# Filtr3.net
KiCad netlist of a schematic drawn in Altium Designer
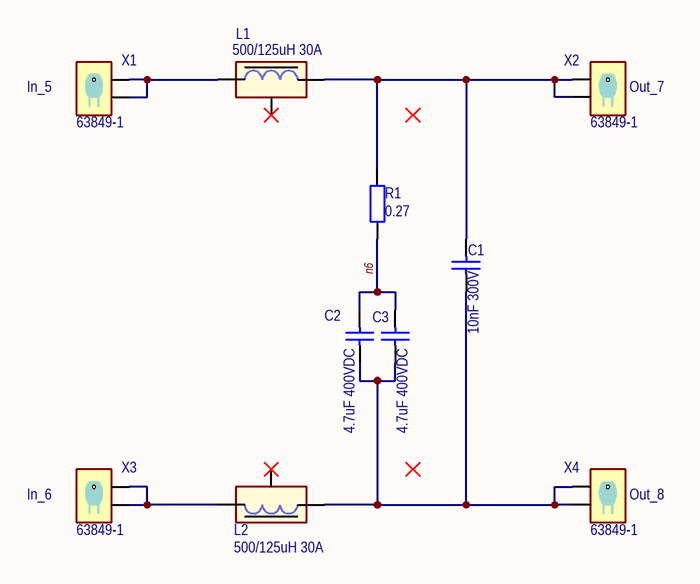
[diagram p0: Filtr3.SchDoc]

(export (version "E")
  (design (tool "Eeschema 10.0.6"))
  (components
    (comp (ref "C1")
      (value "10nF 300V")
      (footprint "mainLib:C Y2 D13 7.5b")
      (description "Ceramic D=14 LS=7.5 300VAC X1Y2")
      (fields (field (name "PARTNUMBER") "DE2F3KY103MA3") (field (name "MANUFACTURER") "Murata"))
      (libsource (lib "mainRCLib") (part "C X1Y2 10nF D13 LS7.5"))
    )
    (comp (ref "C2")
      (value "4.7uF 400VDC")
      (footprint "mainLib:MKP_W20_H39.5_L41.5_LS37.5")
      (description "Polypropelene W20 H39.5 L41.5 LS37.5 400VDC 10%")
      (fields (field (name "PARTNUMBER") "MKP1G044707G00K") (field (name "MANUFACTURER") "Wima"))
      (libsource (lib "mainRCLib") (part "MKP1 4.7uF 10% 400VDC"))
    )
    (comp (ref "C3")
      (value "4.7uF 400VDC")
      (footprint "mainLib:MKP_W20_H39.5_L41.5_LS37.5")
      (description "Polypropelene W20 H39.5 L41.5 LS37.5 400VDC 10%")
      (fields (field (name "PARTNUMBER") "MKP1G044707G00K") (field (name "MANUFACTURER") "Wima"))
      (libsource (lib "mainRCLib") (part "MKP1 4.7uF 10% 400VDC"))
    )
    (comp (ref "L1")
      (value "500/125uH 30A")
      (footprint "mainLib:Dross (500/125 uH 30 A)AMAK.671111.034")
      (description "500/125uH 30A  (Core T250-52 X1)")
      (fields (field (name "MANUFACTURER") "OLTEST") (field (name "PARTNUMBER") "АМАК.671111.034"))
      (libsource (lib "mainLib") (part "Dross 500/125uH 30A АМАК.671111.034"))
    )
    (comp (ref "L2")
      (value "500/125uH 30A")
      (footprint "mainLib:Dross (500/125 uH 30 A)AMAK.671111.034")
      (description "500/125uH 30A  (Core T250-52 X1)")
      (fields (field (name "MANUFACTURER") "OLTEST") (field (name "PARTNUMBER") "АМАК.671111.034"))
      (libsource (lib "") (part "Dross 500/125uH 30A АМАК.671111.034_1"))
    )
    (comp (ref "R1")
      (value "0.27")
      (footprint "mainLib:PRW 5W 1050")
      (description "Выводной PRW 5W 0R27 +-5%")
      (fields (field (name "PARTNUMBER") "PRW05WJW27K") (field (name "MANUFACTURER") "RoyalOhm"))
      (libsource (lib "mainRCLib") (part "PRW 0.27 5W +-5%"))
    )
    (comp (ref "X1")
      (value "63849-1")
      (footprint "63849-1+insulator(154719-1)")
      (description "PCB, 6.3х0.8, hole")
      (fields (field (name "MANUFACTURER") "TE Connectivity"))
      (libsource (lib "") (part "63849-1_1"))
    )
    (comp (ref "X2")
      (value "63849-1")
      (footprint "63849-1+insulator(154719-1)")
      (description "PCB, 6.3х0.8, hole")
      (fields (field (name "MANUFACTURER") "TE Connectivity"))
      (libsource (lib "mainLib") (part "63849-1"))
    )
    (comp (ref "X3")
      (value "63849-1")
      (footprint "63849-1+insulator(154719-1)")
      (description "PCB, 6.3х0.8, hole")
      (fields (field (name "MANUFACTURER") "TE Connectivity"))
      (libsource (lib "") (part "63849-1_1"))
    )
    (comp (ref "X4")
      (value "63849-1")
      (footprint "63849-1+insulator(154719-1)")
      (description "PCB, 6.3х0.8, hole")
      (fields (field (name "MANUFACTURER") "TE Connectivity"))
      (libsource (lib "mainLib") (part "63849-1"))
    )
  )
  (nets
    (net (code "1") (name "/n6") (class "Default")
      (node (ref "C2") (pin "2") (pinfunction "2_2") (pintype "passive"))
      (node (ref "C3") (pin "2") (pinfunction "2_2") (pintype "passive"))
      (node (ref "R1") (pin "1") (pinfunction "1_1") (pintype "passive"))
    )
    (net (code "2") (name "Net-(C1-Pad1)") (class "Default")
      (node (ref "C1") (pin "1") (pinfunction "1_1") (pintype "passive"))
      (node (ref "C2") (pin "1") (pinfunction "1_1") (pintype "passive"))
      (node (ref "C3") (pin "1") (pinfunction "1_1") (pintype "passive"))
      (node (ref "L2") (pin "1") (pinfunction "1_1") (pintype "passive"))
      (node (ref "X4") (pin "1") (pinfunction "1_1") (pintype "passive"))
      (node (ref "X4") (pin "2") (pinfunction "2_2") (pintype "passive"))
    )
    (net (code "3") (name "Net-(C1-Pad2)") (class "Default")
      (node (ref "C1") (pin "2") (pinfunction "2_2") (pintype "passive"))
      (node (ref "L1") (pin "2") (pinfunction "2_2") (pintype "passive"))
      (node (ref "R1") (pin "2") (pinfunction "2_2") (pintype "passive"))
      (node (ref "X2") (pin "1") (pinfunction "1_1") (pintype "passive"))
      (node (ref "X2") (pin "2") (pinfunction "2_2") (pintype "passive"))
    )
    (net (code "4") (name "Net-(L1-Pad1)") (class "Default")
      (node (ref "L1") (pin "1") (pinfunction "1_1") (pintype "passive"))
      (node (ref "X1") (pin "1") (pinfunction "1_1") (pintype "passive"))
      (node (ref "X1") (pin "2") (pinfunction "2_2") (pintype "passive"))
    )
    (net (code "5") (name "Net-(L2-Pad2)") (class "Default")
      (node (ref "L2") (pin "2") (pinfunction "2_2") (pintype "passive"))
      (node (ref "X3") (pin "1") (pinfunction "1_1") (pintype "passive"))
      (node (ref "X3") (pin "2") (pinfunction "2_2") (pintype "passive"))
    )
    (net (code "6") (name "unconnected-(L1-Pad3)") (class "Default")
      (node (ref "L1") (pin "3") (pinfunction "3_3") (pintype "passive+no_connect"))
    )
    (net (code "7") (name "unconnected-(L2-Pad3)") (class "Default")
      (node (ref "L2") (pin "3") (pinfunction "3_3") (pintype "passive+no_connect"))
    )
  )
)
